# Sheet1.net
KiCad netlist of a schematic drawn in Altium Designer
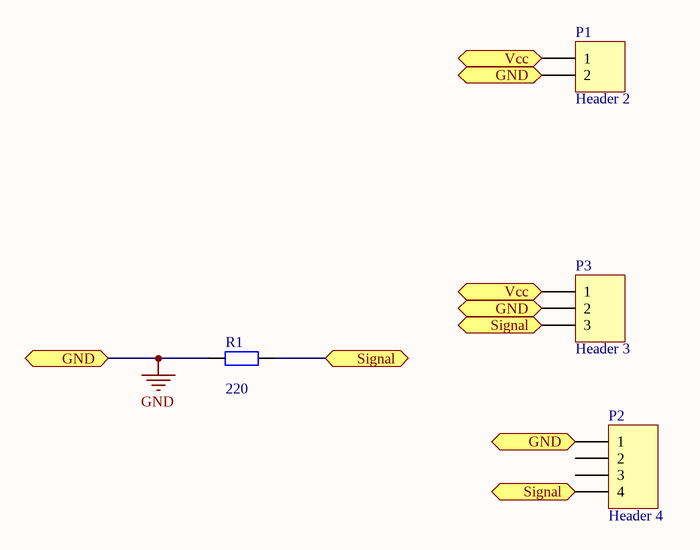
[diagram p0: Sheet1.SchDoc]

(export (version "E")
  (design (tool "Eeschema 10.0.6"))
  (components
    (comp (ref "P1")
      (value "Header 2")
      (footprint "HDR1X2")
      (description "Header, 2-Pin")
      (fields (field (name "PUBLISHER") "Altium Limited"))
      (libsource (lib "Miscellaneous Connectors") (part "Header 2"))
    )
    (comp (ref "P2")
      (value "Header 4")
      (footprint "HDR1X4")
      (description "Header, 4-Pin")
      (fields (field (name "PUBLISHER") "Altium Limited"))
      (libsource (lib "Miscellaneous Connectors") (part "Header 4"))
    )
    (comp (ref "P3")
      (value "Header 3")
      (footprint "HDR1X3")
      (description "Header, 3-Pin")
      (fields (field (name "PUBLISHER") "Altium Limited"))
      (libsource (lib "Miscellaneous Connectors") (part "Header 3"))
    )
    (comp (ref "R1")
      (value "220")
      (footprint "AXIAL-0.4")
      (description "Resistor")
      (fields (field (name "PUBLISHER") "Altium Limited"))
      (libsource (lib "Miscellaneous Devices") (part "Res2"))
    )
  )
  (nets
    (net (code "1") (name "/Signal") (class "Default")
      (node (ref "P2") (pin "4") (pinfunction "4_4") (pintype "passive"))
      (node (ref "P3") (pin "3") (pinfunction "3_3") (pintype "passive"))
      (node (ref "R1") (pin "1") (pinfunction "1_1") (pintype "passive"))
    )
    (net (code "2") (name "/Vcc") (class "Default")
      (node (ref "P1") (pin "1") (pinfunction "1_1") (pintype "passive"))
      (node (ref "P3") (pin "1") (pinfunction "1_1") (pintype "passive"))
    )
    (net (code "3") (name "GND") (class "Default")
      (node (ref "P1") (pin "2") (pinfunction "2_2") (pintype "passive"))
      (node (ref "P2") (pin "1") (pinfunction "1_1") (pintype "passive"))
      (node (ref "P3") (pin "2") (pinfunction "2_2") (pintype "passive"))
      (node (ref "R1") (pin "2") (pinfunction "2_2") (pintype "passive"))
    )
    (net (code "4") (name "unconnected-(P2-Pad2)") (class "Default")
      (node (ref "P2") (pin "2") (pinfunction "2_2") (pintype "passive"))
    )
    (net (code "5") (name "unconnected-(P2-Pad3)") (class "Default")
      (node (ref "P2") (pin "3") (pinfunction "3_3") (pintype "passive"))
    )
  )
)
